# mini-usb-con.net
KiCad netlist of a schematic drawn in EAGLE
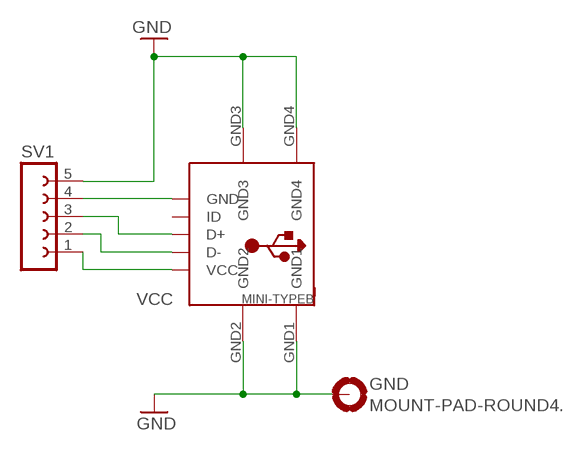
[diagram p0: schematic, sheet 1]

(export (version "E")
  (design (tool "Eeschema 10.0.6"))
  (components
    (comp (ref "GND")
      (value "MOUNT-PAD-ROUND4.1")
      (footprint "eagle-import:4,1-PAD")
      (libsource (lib "eagle-import") (part "MOUNT-PAD-ROUND4.1"))
    )
    (comp (ref "MINI-TYPEB")
      (value "USBTHM")
      (footprint "eagle-import:USB-MINIB-THM")
      (libsource (lib "eagle-import") (part "USBTHM"))
    )
    (comp (ref "SV1")
      (value "FE05-1")
      (footprint "eagle-import:FE05-1")
      (libsource (lib "eagle-import") (part "FE05-1"))
    )
  )
  (nets
    (net (code "1") (name "/VCC") (class "Default")
      (node (ref "MINI-TYPEB") (pin "VCC") (pinfunction "VCC_VCC") (pintype "power_in"))
      (node (ref "SV1") (pin "1") (pinfunction "1_1") (pintype "passive"))
    )
    (net (code "2") (name "GND") (class "Default")
      (node (ref "GND") (pin "B4,1") (pinfunction "MOUNT_B4,1") (pintype "passive"))
      (node (ref "MINI-TYPEB") (pin "GND1") (pinfunction "GND1_GND1") (pintype "power_in"))
      (node (ref "MINI-TYPEB") (pin "GND2") (pinfunction "GND2_GND2") (pintype "power_in"))
      (node (ref "MINI-TYPEB") (pin "GND3") (pinfunction "GND3_GND3") (pintype "power_in"))
      (node (ref "MINI-TYPEB") (pin "GND4") (pinfunction "GND4_GND4") (pintype "power_in"))
      (node (ref "SV1") (pin "5") (pinfunction "5_5") (pintype "passive"))
    )
    (net (code "3") (name "Net-(MINI-TYPEB-PadD+)") (class "Default")
      (node (ref "MINI-TYPEB") (pin "D+") (pinfunction "D+_D+") (pintype "bidirectional"))
      (node (ref "SV1") (pin "3") (pinfunction "3_3") (pintype "passive"))
    )
    (net (code "4") (name "Net-(MINI-TYPEB-PadD-)") (class "Default")
      (node (ref "MINI-TYPEB") (pin "D-") (pinfunction "D-_D-") (pintype "bidirectional"))
      (node (ref "SV1") (pin "2") (pinfunction "2_2") (pintype "passive"))
    )
    (net (code "5") (name "Net-(MINI-TYPEB-PadGND)") (class "Default")
      (node (ref "MINI-TYPEB") (pin "GND") (pinfunction "GND_GND") (pintype "power_in"))
      (node (ref "SV1") (pin "4") (pinfunction "4_4") (pintype "passive"))
    )
    (net (code "6") (name "unconnected-(MINI-TYPEB-PadID)") (class "Default")
      (node (ref "MINI-TYPEB") (pin "ID") (pinfunction "ID_ID") (pintype "bidirectional"))
    )
  )
)
